# Microcontroller.net
KiCad netlist of a schematic drawn in Altium Designer
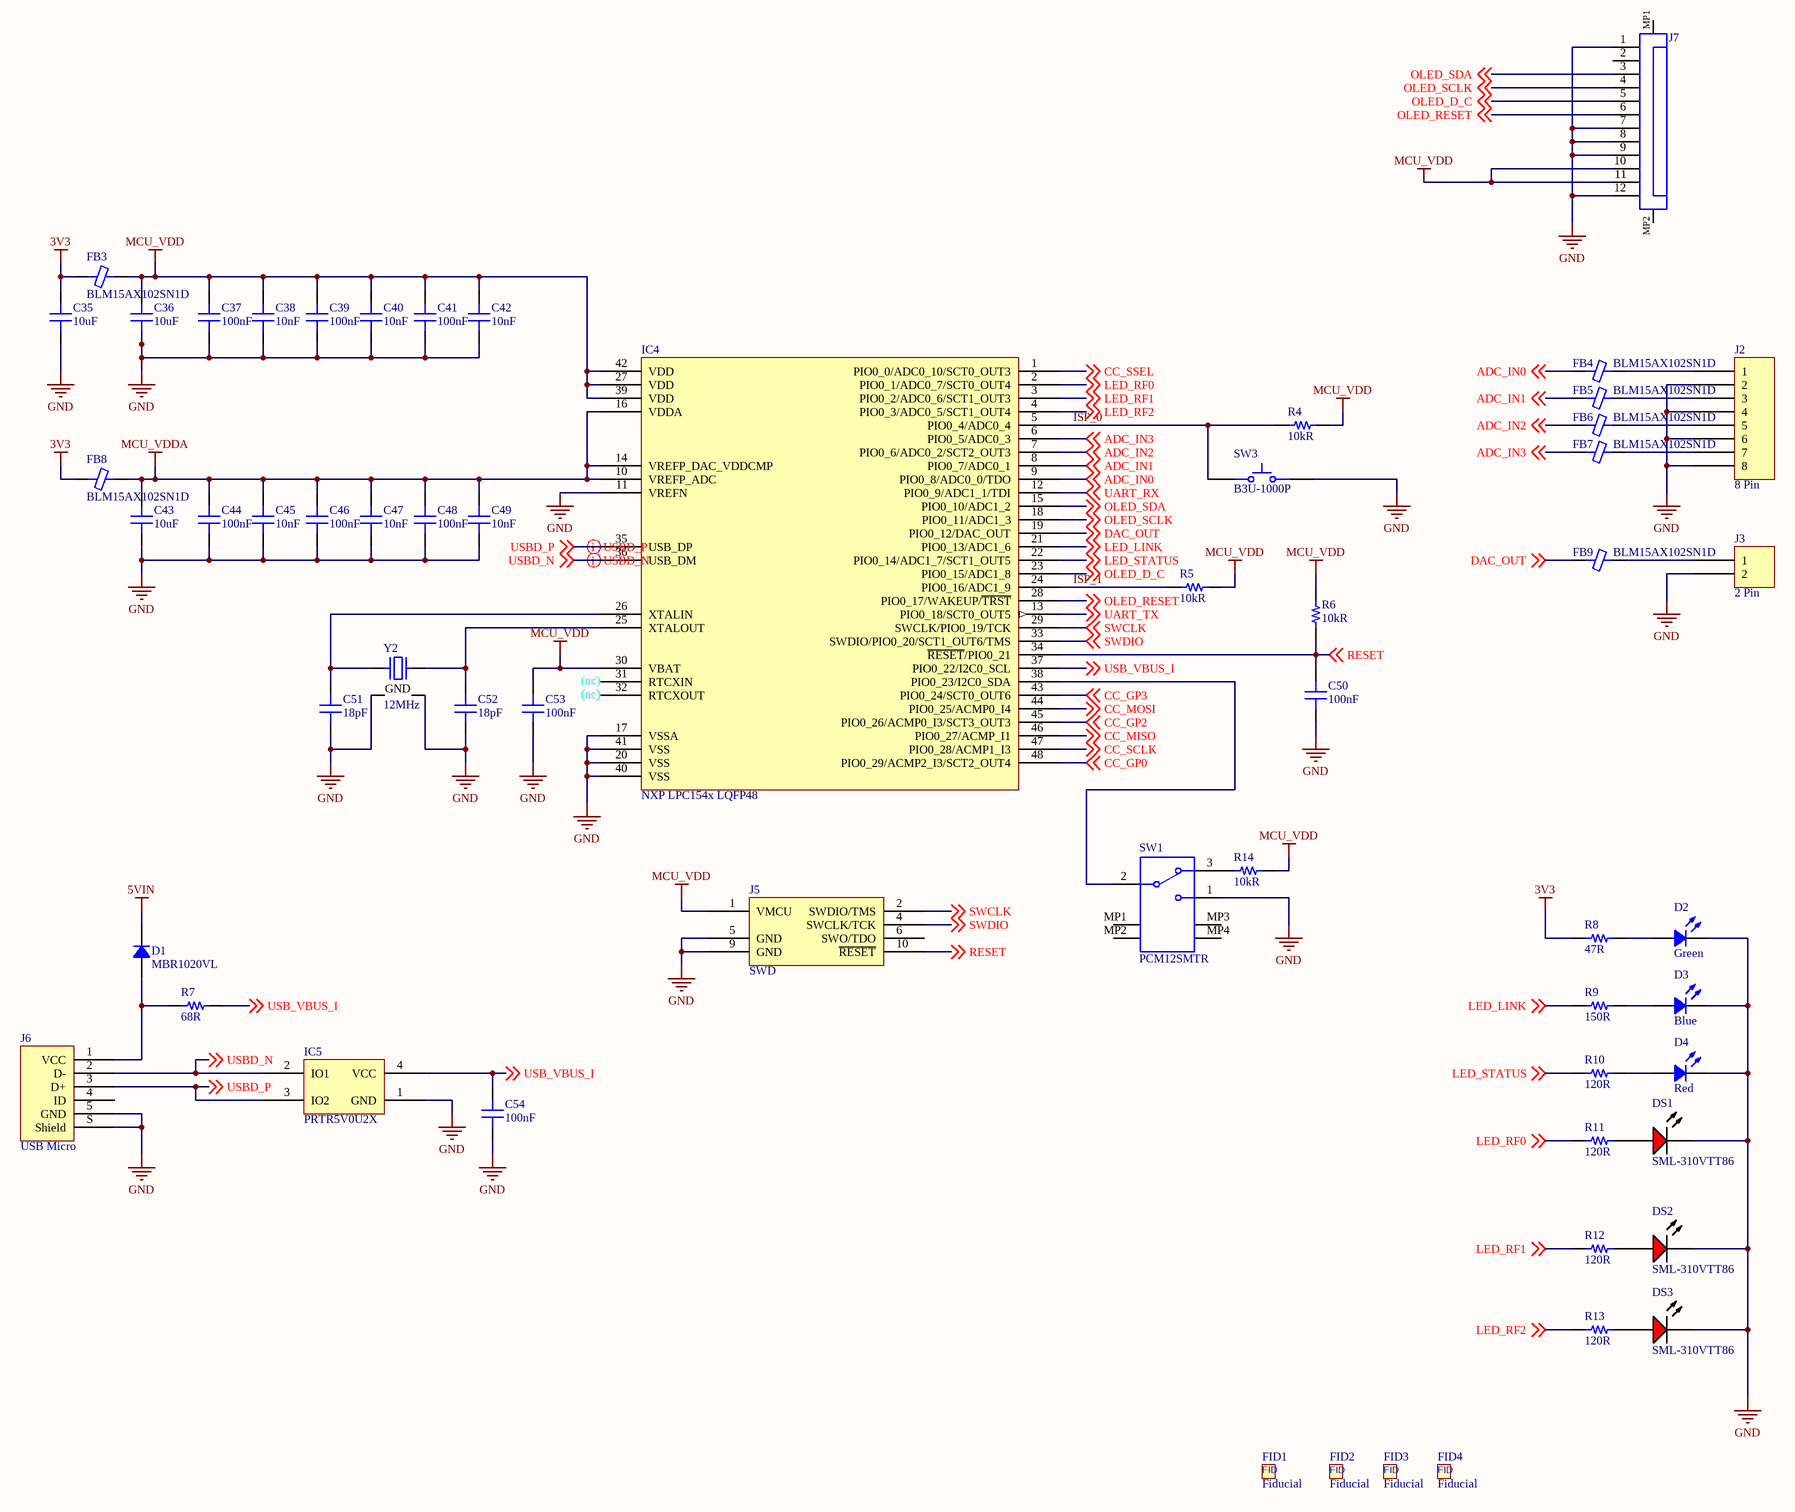
[diagram p0: Microcontroller.SchDoc]

(export (version "E")
  (design (tool "Eeschema 10.0.6"))
  (components
    (comp (ref "C35")
      (value "10uF")
      (footprint "CAP 0805/2012")
      (description "Cap Ceramic 10uF 10V X5R 10% SMD 0805 85C Embossed T/R")
      (fields (field (name "TOLERANCE") "10%") (field (name "VOLTAGE") "10V"))
      (libsource (lib "SCH - PASSIVES - CAPACITOR") (part "Capacitor"))
    )
    (comp (ref "C36")
      (value "10uF")
      (footprint "CAP 0805/2012")
      (description "Cap Ceramic 10uF 10V X5R 10% SMD 0805 85C Embossed T/R")
      (fields (field (name "TOLERANCE") "10%") (field (name "VOLTAGE") "10V"))
      (libsource (lib "SCH - PASSIVES - CAPACITOR") (part "Capacitor"))
    )
    (comp (ref "C37")
      (value "100nF")
      (footprint "CAP 0402/1005")
      (description "Cap Ceramic 0.1uF 10V X5R 20% Pad SMD 0402 85C T/R")
      (fields (field (name "TOLERANCE") "20%"))
      (libsource (lib "SCH - PASSIVES - CAPACITOR") (part "Capacitor"))
    )
    (comp (ref "C38")
      (value "10nF")
      (footprint "CAP 0402/1005")
      (description "TAIYO YUDEN - TMK105B7103KV-F - CERAMIC CAPACITOR 0.01UF, 25V, X7R, 10%, 0402, FULL REEL")
      (fields (field (name "TOLERANCE") "10%") (field (name "VOLTAGE") "25V"))
      (libsource (lib "SCH - PASSIVES - CAPACITOR") (part "Capacitor"))
    )
    (comp (ref "C39")
      (value "100nF")
      (footprint "CAP 0402/1005")
      (description "Cap Ceramic 0.1uF 10V X5R 20% Pad SMD 0402 85C T/R")
      (fields (field (name "TOLERANCE") "20%"))
      (libsource (lib "SCH - PASSIVES - CAPACITOR") (part "Capacitor"))
    )
    (comp (ref "C40")
      (value "10nF")
      (footprint "CAP 0402/1005")
      (description "TAIYO YUDEN - TMK105B7103KV-F - CERAMIC CAPACITOR 0.01UF, 25V, X7R, 10%, 0402, FULL REEL")
      (fields (field (name "TOLERANCE") "10%") (field (name "VOLTAGE") "25V"))
      (libsource (lib "SCH - PASSIVES - CAPACITOR") (part "Capacitor"))
    )
    (comp (ref "C41")
      (value "100nF")
      (footprint "CAP 0402/1005")
      (description "Cap Ceramic 0.1uF 10V X5R 20% Pad SMD 0402 85C T/R")
      (fields (field (name "TOLERANCE") "20%"))
      (libsource (lib "SCH - PASSIVES - CAPACITOR") (part "Capacitor"))
    )
    (comp (ref "C42")
      (value "10nF")
      (footprint "CAP 0402/1005")
      (description "TAIYO YUDEN - TMK105B7103KV-F - CERAMIC CAPACITOR 0.01UF, 25V, X7R, 10%, 0402, FULL REEL")
      (fields (field (name "TOLERANCE") "10%") (field (name "VOLTAGE") "25V"))
      (libsource (lib "SCH - PASSIVES - CAPACITOR") (part "Capacitor"))
    )
    (comp (ref "C43")
      (value "10uF")
      (footprint "CAP 0805/2012")
      (description "Cap Ceramic 10uF 10V X5R 10% SMD 0805 85C Embossed T/R")
      (fields (field (name "TOLERANCE") "10%") (field (name "VOLTAGE") "10V"))
      (libsource (lib "SCH - PASSIVES - CAPACITOR") (part "Capacitor"))
    )
    (comp (ref "C44")
      (value "100nF")
      (footprint "CAP 0402/1005")
      (description "Cap Ceramic 0.1uF 10V X5R 20% Pad SMD 0402 85C T/R")
      (fields (field (name "TOLERANCE") "20%"))
      (libsource (lib "SCH - PASSIVES - CAPACITOR") (part "Capacitor"))
    )
    (comp (ref "C45")
      (value "10nF")
      (footprint "CAP 0402/1005")
      (description "TAIYO YUDEN - TMK105B7103KV-F - CERAMIC CAPACITOR 0.01UF, 25V, X7R, 10%, 0402, FULL REEL")
      (fields (field (name "TOLERANCE") "10%") (field (name "VOLTAGE") "25V"))
      (libsource (lib "SCH - PASSIVES - CAPACITOR") (part "Capacitor"))
    )
    (comp (ref "C46")
      (value "100nF")
      (footprint "CAP 0402/1005")
      (description "Cap Ceramic 0.1uF 10V X5R 20% Pad SMD 0402 85C T/R")
      (fields (field (name "TOLERANCE") "20%"))
      (libsource (lib "SCH - PASSIVES - CAPACITOR") (part "Capacitor"))
    )
    (comp (ref "C47")
      (value "10nF")
      (footprint "CAP 0402/1005")
      (description "TAIYO YUDEN - TMK105B7103KV-F - CERAMIC CAPACITOR 0.01UF, 25V, X7R, 10%, 0402, FULL REEL")
      (fields (field (name "TOLERANCE") "10%") (field (name "VOLTAGE") "25V"))
      (libsource (lib "SCH - PASSIVES - CAPACITOR") (part "Capacitor"))
    )
    (comp (ref "C48")
      (value "100nF")
      (footprint "CAP 0402/1005")
      (description "Cap Ceramic 0.1uF 10V X5R 20% Pad SMD 0402 85C T/R")
      (fields (field (name "TOLERANCE") "20%"))
      (libsource (lib "SCH - PASSIVES - CAPACITOR") (part "Capacitor"))
    )
    (comp (ref "C49")
      (value "10nF")
      (footprint "CAP 0402/1005")
      (description "TAIYO YUDEN - TMK105B7103KV-F - CERAMIC CAPACITOR 0.01UF, 25V, X7R, 10%, 0402, FULL REEL")
      (fields (field (name "TOLERANCE") "10%") (field (name "VOLTAGE") "25V"))
      (libsource (lib "SCH - PASSIVES - CAPACITOR") (part "Capacitor"))
    )
    (comp (ref "C50")
      (value "100nF")
      (footprint "CAP 0402/1005")
      (description "Cap Ceramic 0.1uF 10V X5R 20% Pad SMD 0402 85C T/R")
      (fields (field (name "TOLERANCE") "20%"))
      (libsource (lib "SCH - PASSIVES - CAPACITOR") (part "Capacitor"))
    )
    (comp (ref "C51")
      (value "18pF")
      (footprint "CAP 0402/1005")
      (description "CAP CER 18PF 50V C0G/NPO 0402")
      (fields (field (name "TOLERANCE") "5%") (field (name "VOLTAGE") "50V"))
      (libsource (lib "SCH - PASSIVES - CAPACITOR") (part "Capacitor"))
    )
    (comp (ref "C52")
      (value "18pF")
      (footprint "CAP 0402/1005")
      (description "CAP CER 18PF 50V C0G/NPO 0402")
      (fields (field (name "TOLERANCE") "5%") (field (name "VOLTAGE") "50V"))
      (libsource (lib "SCH - PASSIVES - CAPACITOR") (part "Capacitor"))
    )
    (comp (ref "C53")
      (value "100nF")
      (footprint "CAP 0402/1005")
      (description "Cap Ceramic 0.1uF 10V X5R 20% Pad SMD 0402 85C T/R")
      (fields (field (name "TOLERANCE") "20%"))
      (libsource (lib "SCH - PASSIVES - CAPACITOR") (part "Capacitor"))
    )
    (comp (ref "C54")
      (value "100nF")
      (footprint "CAP 0402/1005")
      (description "Cap Ceramic 0.1uF 10V X5R 20% Pad SMD 0402 85C T/R")
      (fields (field (name "TOLERANCE") "20%"))
      (libsource (lib "SCH - PASSIVES - CAPACITOR") (part "Capacitor"))
    )
    (comp (ref "D1")
      (value "MBR1020VL")
      (footprint "SOD123F")
      (description "DIODE SCHOTTKY 20V 1A SOD123F")
      (libsource (lib "SCH - DIODES - DIODE") (part "Diode"))
    )
    (comp (ref "D2")
      (value "Green")
      (footprint "LED 0603/1608 GREEN")
      (description "0603 green led allngap 571nm-574nm water clear 18-71mcd 130d")
      (libsource (lib "SCH - DIODES - LED") (part "LED"))
    )
    (comp (ref "D3")
      (value "Blue")
      (footprint "LED 0603/1608 BLUE")
      (description "LED Uni-Color Blue 468nm 2-Pin Chip 0603(1608Metric) T/R")
      (libsource (lib "SCH - DIODES - LED") (part "LED"))
    )
    (comp (ref "D4")
      (value "Red")
      (footprint "LED 0603/1608 RED")
      (description "LED RED DIFFUSED 1608 SMD")
      (libsource (lib "SCH - DIODES - LED") (part "LED"))
    )
    (comp (ref "DS1")
      (value "SML-310VTT86")
      (footprint "ROHM-SML-31X_V")
      (fields (field (name "MANUFACTURER") "Rohm"))
      (libsource (lib "Altium Content Vault") (part "LED-RED-AK-2"))
    )
    (comp (ref "DS2")
      (value "SML-310VTT86")
      (footprint "ROHM-SML-31X_V")
      (fields (field (name "MANUFACTURER") "Rohm"))
      (libsource (lib "Altium Content Vault") (part "LED-RED-AK-2"))
    )
    (comp (ref "DS3")
      (value "SML-310VTT86")
      (footprint "ROHM-SML-31X_V")
      (fields (field (name "MANUFACTURER") "Rohm"))
      (libsource (lib "Altium Content Vault") (part "LED-RED-AK-2"))
    )
    (comp (ref "FB3")
      (value "BLM15AX102SN1D")
      (footprint "FER 0402/1005")
      (description "Ferrite Beads Multi-Layer 1KOhm 25% 100MHz 350mA 490mOhm DCR 0402 T/R")
      (fields (field (name "TOLERANCE") "25%"))
      (libsource (lib "SCH - PASSIVES - FERRITE CHIP") (part "Ferrite Chip"))
    )
    (comp (ref "FB4")
      (value "BLM15AX102SN1D")
      (footprint "FER 0402/1005")
      (description "Ferrite Beads Multi-Layer 1KOhm 25% 100MHz 350mA 490mOhm DCR 0402 T/R")
      (fields (field (name "TOLERANCE") "25%"))
      (libsource (lib "SCH - PASSIVES - FERRITE CHIP") (part "Ferrite Chip"))
    )
    (comp (ref "FB5")
      (value "BLM15AX102SN1D")
      (footprint "FER 0402/1005")
      (description "Ferrite Beads Multi-Layer 1KOhm 25% 100MHz 350mA 490mOhm DCR 0402 T/R")
      (fields (field (name "TOLERANCE") "25%"))
      (libsource (lib "SCH - PASSIVES - FERRITE CHIP") (part "Ferrite Chip"))
    )
    (comp (ref "FB6")
      (value "BLM15AX102SN1D")
      (footprint "FER 0402/1005")
      (description "Ferrite Beads Multi-Layer 1KOhm 25% 100MHz 350mA 490mOhm DCR 0402 T/R")
      (fields (field (name "TOLERANCE") "25%"))
      (libsource (lib "SCH - PASSIVES - FERRITE CHIP") (part "Ferrite Chip"))
    )
    (comp (ref "FB7")
      (value "BLM15AX102SN1D")
      (footprint "FER 0402/1005")
      (description "Ferrite Beads Multi-Layer 1KOhm 25% 100MHz 350mA 490mOhm DCR 0402 T/R")
      (fields (field (name "TOLERANCE") "25%"))
      (libsource (lib "SCH - PASSIVES - FERRITE CHIP") (part "Ferrite Chip"))
    )
    (comp (ref "FB8")
      (value "BLM15AX102SN1D")
      (footprint "FER 0402/1005")
      (description "Ferrite Beads Multi-Layer 1KOhm 25% 100MHz 350mA 490mOhm DCR 0402 T/R")
      (fields (field (name "TOLERANCE") "25%"))
      (libsource (lib "SCH - PASSIVES - FERRITE CHIP") (part "Ferrite Chip"))
    )
    (comp (ref "FB9")
      (value "BLM15AX102SN1D")
      (footprint "FER 0402/1005")
      (description "Ferrite Beads Multi-Layer 1KOhm 25% 100MHz 350mA 490mOhm DCR 0402 T/R")
      (fields (field (name "TOLERANCE") "25%"))
      (libsource (lib "SCH - PASSIVES - FERRITE CHIP") (part "Ferrite Chip"))
    )
    (comp (ref "FID1") (value "Fiducial") (footprint "Fiducial") (libsource (lib "Useful") (part "Fiducial")))
    (comp (ref "FID2") (value "Fiducial") (footprint "Fiducial") (libsource (lib "Useful") (part "Fiducial")))
    (comp (ref "FID3") (value "Fiducial") (footprint "Fiducial") (libsource (lib "Useful") (part "Fiducial")))
    (comp (ref "FID4") (value "Fiducial") (footprint "Fiducial") (libsource (lib "Useful") (part "Fiducial")))
    (comp (ref "IC4")
      (value "NXP LPC154x LQFP48")
      (footprint "NXP LQFP-48 7x7mm")
      (description "IC MCU 32BIT 256KB FLASH 48LQFP")
      (libsource (lib "SCH - ARM CORTEX - NXP LPC154X LQFP48") (part "NXP LPC154x LQFP48"))
    )
    (comp (ref "IC5")
      (value "PRTR5V0U2X")
      (footprint "SOT143B")
      (description "TVS DIODE 5.5V SOT143B")
      (libsource (lib "SCH - DIODES - NXP PRTR5V0U2X") (part "NXP PRTR5V0U2X"))
    )
    (comp (ref "J2")
      (value "8 Pin")
      (footprint "FCI 06-381-8PIN")
      (description "TERM BLOCK HDR 8POS 90DEG 3.81MM")
      (libsource (lib "SCH - CONNECTORS - 8 PIN") (part "8 Pin"))
    )
    (comp (ref "J3")
      (value "2 Pin")
      (footprint "FCI 06-381-2PIN")
      (description "TERM BLOCK HDR 2POS 90DEG 3.81MM")
      (libsource (lib "SCH - CONNECTORS - 2 PIN") (part "2 Pin"))
    )
    (comp (ref "J5") (value "SWD") (footprint "10 Pin SWD") (libsource (lib "Useful") (part "SWD")))
    (comp (ref "J6")
      (value "USB Micro")
      (footprint "FCI USB 10118193-0001LF")
      (description "CONN RCPT USB2.0 MICRO B SMD R/A")
      (libsource (lib "SCH - CONNECTORS - USB 2.0 TYPE B MICRO") (part "USB 2.0 Type B Micro"))
    )
    (comp (ref "J7")
      (value "687112183722")
      (footprint "687112183722")
      (description "SMT ZIF Connectors Low Profile WR-FPC, Horizontal, Bottom Contact, pitch 0.5 mm, 12 pins")
      (fields (field (name "MANUFACTURER") "Wurth Elektronik") (field (name "PUBLISHER") "WurthElektronik"))
      (libsource (lib "Altium Content Vault") (part "WE-68X1121XXX22-12"))
    )
    (comp (ref "R4")
      (value "10kR")
      (footprint "RES 0402/1005")
      (description "RES 10K OHM 5% 1/16W 0402")
      (fields (field (name "TOLERANCE") "5%"))
      (libsource (lib "SCH - PASSIVES - RESISTOR") (part "Resistor"))
    )
    (comp (ref "R5")
      (value "10kR")
      (footprint "RES 0402/1005")
      (description "RES 10K OHM 5% 1/16W 0402")
      (fields (field (name "TOLERANCE") "5%"))
      (libsource (lib "SCH - PASSIVES - RESISTOR") (part "Resistor"))
    )
    (comp (ref "R6")
      (value "10kR")
      (footprint "RES 0402/1005")
      (description "RES 10K OHM 5% 1/16W 0402")
      (fields (field (name "TOLERANCE") "5%"))
      (libsource (lib "SCH - PASSIVES - RESISTOR") (part "Resistor"))
    )
    (comp (ref "R7")
      (value "68R")
      (footprint "RES 0402/1005")
      (description "RES SMD 68 OHM 5% 1/16W 0402")
      (fields (field (name "TOLERANCE") "5%"))
      (libsource (lib "SCH - PASSIVES - RESISTOR") (part "Resistor"))
    )
    (comp (ref "R8")
      (value "47R")
      (footprint "RES 0402/1005")
      (description "KOA SPEAR ELECTRONICS - RK73B1JTTD470J - RES, 47R, 5%, 0.1W, 0603, THICK FILM")
      (fields (field (name "TOLERANCE") "5%"))
      (libsource (lib "SCH - PASSIVES - RESISTOR") (part "Resistor"))
    )
    (comp (ref "R9")
      (value "150R")
      (footprint "RES 0402/1005")
      (description "Res Thick Film 0603 150 Ohm 5% 0.1W(1/10W) ±200ppm/C Molded SMD Automotive Punched Paper T/R")
      (fields (field (name "TOLERANCE") "5%"))
      (libsource (lib "SCH - PASSIVES - RESISTOR") (part "Resistor"))
    )
    (comp (ref "R10")
      (value "120R")
      (footprint "RES 0402/1005")
      (fields (field (name "TOLERANCE") "5%"))
      (libsource (lib "SCH - PASSIVES - RESISTOR") (part "Resistor"))
    )
    (comp (ref "R11")
      (value "120R")
      (footprint "RES 0402/1005")
      (fields (field (name "TOLERANCE") "5%"))
      (libsource (lib "SCH - PASSIVES - RESISTOR") (part "Resistor"))
    )
    (comp (ref "R12")
      (value "120R")
      (footprint "RES 0402/1005")
      (fields (field (name "TOLERANCE") "5%"))
      (libsource (lib "SCH - PASSIVES - RESISTOR") (part "Resistor"))
    )
    (comp (ref "R13")
      (value "120R")
      (footprint "RES 0402/1005")
      (fields (field (name "TOLERANCE") "5%"))
      (libsource (lib "SCH - PASSIVES - RESISTOR") (part "Resistor"))
    )
    (comp (ref "R14")
      (value "10kR")
      (footprint "RES 0402/1005")
      (description "RES 10K OHM 5% 1/16W 0402")
      (fields (field (name "TOLERANCE") "5%"))
      (libsource (lib "SCH - PASSIVES - RESISTOR") (part "Resistor"))
    )
    (comp (ref "SW1")
      (value "PCM12SMTR")
      (footprint "CKCP-PCM12SMTR_V")
      (description "Ultraminiature Slide Switch, SPDT, 0.3 A, 6 V, -20 to 85 degC, 3-Pin SMD, RoHS, Tape and Reel")
      (fields (field (name "MANUFACTURER") "C&K Components"))
      (libsource (lib "Altium Content Vault") (part "SW-SPDT-3_A"))
    )
    (comp (ref "SW3")
      (value "B3U-1000P")
      (footprint "OMRON-B3U-1000_V")
      (description "Ultra-Small Tactile Switch, 0.05 A, 12 V, -25 to 70 degC, 2-Pin SMD, RoHS, Tape and Reel")
      (fields (field (name "MANUFACTURER") "Omron Electronic Components"))
      (libsource (lib "Altium Content Vault") (part "SW-SPST-NO-2"))
    )
    (comp (ref "Y2")
      (value "12MHz")
      (footprint "ABRACON ABM8G")
      (description "CRYSTAL 12.0000MHZ 18PF SMD")
      (fields (field (name "TOLERANCE") "20ppm"))
      (libsource (lib "SCH - CRYSTALS - ABRACON CRYSTAL ABM8G") (part "Abracon Crystal ABM8G"))
    )
  )
  (nets
    (net (code "1") (name "/ISP_0") (class "Default")
      (node (ref "IC4") (pin "5") (pinfunction "PIO0_4/ADC0_4_5") (pintype "passive"))
      (node (ref "R4") (pin "2") (pinfunction "2_2") (pintype "passive"))
      (node (ref "SW3") (pin "1") (pinfunction "1_1") (pintype "passive"))
    )
    (net (code "2") (name "/ISP_1") (class "Default")
      (node (ref "IC4") (pin "24") (pinfunction "PIO0_16/ADC1_9_24") (pintype "passive"))
      (node (ref "R5") (pin "2") (pinfunction "2_2") (pintype "passive"))
    )
    (net (code "3") (name "3V3") (class "Default")
      (node (ref "C35") (pin "2") (pinfunction "2_2") (pintype "passive"))
      (node (ref "FB3") (pin "2") (pinfunction "2_2") (pintype "passive"))
      (node (ref "FB8") (pin "2") (pinfunction "2_2") (pintype "passive"))
      (node (ref "R8") (pin "1") (pinfunction "1_1") (pintype "passive"))
    )
    (net (code "4") (name "5VIN") (class "Default")
      (node (ref "D1") (pin "2") (pinfunction "2_2") (pintype "passive"))
    )
    (net (code "5") (name "ADC_IN0") (class "Default")
      (node (ref "FB4") (pin "2") (pinfunction "2_2") (pintype "passive"))
      (node (ref "IC4") (pin "9") (pinfunction "PIO0_8/ADC0_0/TDO_9") (pintype "passive"))
    )
    (net (code "6") (name "ADC_IN1") (class "Default")
      (node (ref "FB5") (pin "2") (pinfunction "2_2") (pintype "passive"))
      (node (ref "IC4") (pin "8") (pinfunction "PIO0_7/ADC0_1_8") (pintype "passive"))
    )
    (net (code "7") (name "ADC_IN2") (class "Default")
      (node (ref "FB6") (pin "2") (pinfunction "2_2") (pintype "passive"))
      (node (ref "IC4") (pin "7") (pinfunction "PIO0_6/ADC0_2/SCT2_OUT3_7") (pintype "passive"))
    )
    (net (code "8") (name "ADC_IN3") (class "Default")
      (node (ref "FB7") (pin "2") (pinfunction "2_2") (pintype "passive"))
      (node (ref "IC4") (pin "6") (pinfunction "PIO0_5/ADC0_3_6") (pintype "passive"))
    )
    (net (code "9") (name "CC_GP0") (class "Default")
      (node (ref "IC4") (pin "48") (pinfunction "PIO0_29/ACMP2_I3/SCT2_OUT4_48") (pintype "passive"))
    )
    (net (code "10") (name "CC_GP2") (class "Default")
      (node (ref "IC4") (pin "45") (pinfunction "PIO0_26/ACMP0_I3/SCT3_OUT3_45") (pintype "passive"))
    )
    (net (code "11") (name "CC_GP3") (class "Default")
      (node (ref "IC4") (pin "43") (pinfunction "PIO0_24/SCT0_OUT6_43") (pintype "passive"))
    )
    (net (code "12") (name "CC_MISO") (class "Default")
      (node (ref "IC4") (pin "46") (pinfunction "PIO0_27/ACMP_I1_46") (pintype "passive"))
    )
    (net (code "13") (name "CC_MOSI") (class "Default")
      (node (ref "IC4") (pin "44") (pinfunction "PIO0_25/ACMP0_I4_44") (pintype "passive"))
    )
    (net (code "14") (name "CC_SCLK") (class "Default")
      (node (ref "IC4") (pin "47") (pinfunction "PIO0_28/ACMP1_I3_47") (pintype "passive"))
    )
    (net (code "15") (name "CC_SSEL") (class "Default")
      (node (ref "IC4") (pin "1") (pinfunction "PIO0_0/ADC0_10/SCT0_OUT3_1") (pintype "passive"))
    )
    (net (code "16") (name "DAC_OUT") (class "Default")
      (node (ref "FB9") (pin "2") (pinfunction "2_2") (pintype "passive"))
      (node (ref "IC4") (pin "19") (pinfunction "PIO0_12/DAC_OUT_19") (pintype "passive"))
    )
    (net (code "17") (name "GND") (class "Default")
      (node (ref "C35") (pin "1") (pinfunction "1_1") (pintype "passive"))
      (node (ref "C36") (pin "1") (pinfunction "1_1") (pintype "passive"))
      (node (ref "C37") (pin "1") (pinfunction "1_1") (pintype "passive"))
      (node (ref "C38") (pin "1") (pinfunction "1_1") (pintype "passive"))
      (node (ref "C39") (pin "1") (pinfunction "1_1") (pintype "passive"))
      (node (ref "C40") (pin "1") (pinfunction "1_1") (pintype "passive"))
      (node (ref "C41") (pin "1") (pinfunction "1_1") (pintype "passive"))
      (node (ref "C42") (pin "1") (pinfunction "1_1") (pintype "passive"))
      (node (ref "C43") (pin "1") (pinfunction "1_1") (pintype "passive"))
      (node (ref "C44") (pin "1") (pinfunction "1_1") (pintype "passive"))
      (node (ref "C45") (pin "1") (pinfunction "1_1") (pintype "passive"))
      (node (ref "C46") (pin "1") (pinfunction "1_1") (pintype "passive"))
      (node (ref "C47") (pin "1") (pinfunction "1_1") (pintype "passive"))
      (node (ref "C48") (pin "1") (pinfunction "1_1") (pintype "passive"))
      (node (ref "C49") (pin "1") (pinfunction "1_1") (pintype "passive"))
      (node (ref "C50") (pin "1") (pinfunction "1_1") (pintype "passive"))
      (node (ref "C51") (pin "1") (pinfunction "1_1") (pintype "passive"))
      (node (ref "C52") (pin "1") (pinfunction "1_1") (pintype "passive"))
      (node (ref "C53") (pin "1") (pinfunction "1_1") (pintype "passive"))
      (node (ref "C54") (pin "1") (pinfunction "1_1") (pintype "passive"))
      (node (ref "D2") (pin "2") (pinfunction "2_2") (pintype "passive"))
      (node (ref "D3") (pin "2") (pinfunction "2_2") (pintype "passive"))
      (node (ref "D4") (pin "2") (pinfunction "2_2") (pintype "passive"))
      (node (ref "DS1") (pin "2") (pinfunction "K_2") (pintype "passive"))
      (node (ref "DS2") (pin "2") (pinfunction "K_2") (pintype "passive"))
      (node (ref "DS3") (pin "2") (pinfunction "K_2") (pintype "passive"))
      (node (ref "IC4") (pin "11") (pinfunction "VREFN_11") (pintype "passive"))
      (node (ref "IC4") (pin "17") (pinfunction "VSSA_17") (pintype "passive"))
      (node (ref "IC4") (pin "20") (pinfunction "VSS_20") (pintype "passive"))
      (node (ref "IC4") (pin "40") (pinfunction "VSS_40") (pintype "passive"))
      (node (ref "IC4") (pin "41") (pinfunction "VSS_41") (pintype "passive"))
      (node (ref "IC5") (pin "1") (pinfunction "GND_1") (pintype "passive"))
      (node (ref "J2") (pin "2") (pinfunction "2_2") (pintype "passive"))
      (node (ref "J2") (pin "4") (pinfunction "4_4") (pintype "passive"))
      (node (ref "J2") (pin "6") (pinfunction "6_6") (pintype "passive"))
      (node (ref "J2") (pin "8") (pinfunction "8_8") (pintype "passive"))
      (node (ref "J3") (pin "2") (pinfunction "2_2") (pintype "passive"))
      (node (ref "J5") (pin "5") (pinfunction "GND_5") (pintype "passive"))
      (node (ref "J5") (pin "9") (pinfunction "GND_9") (pintype "passive"))
      (node (ref "J6") (pin "5") (pinfunction "GND_5") (pintype "passive"))
      (node (ref "J6") (pin "S") (pinfunction "Shield_S") (pintype "passive"))
      (node (ref "J7") (pin "1") (pinfunction "1_1") (pintype "passive"))
      (node (ref "J7") (pin "12") (pinfunction "12_12") (pintype "passive"))
      (node (ref "J7") (pin "7") (pinfunction "7_7") (pintype "passive"))
      (node (ref "J7") (pin "8") (pinfunction "8_8") (pintype "passive"))
      (node (ref "J7") (pin "9") (pinfunction "9_9") (pintype "passive"))
      (node (ref "SW1") (pin "1") (pinfunction "1_1") (pintype "passive"))
      (node (ref "SW3") (pin "2") (pinfunction "2_2") (pintype "passive"))
      (node (ref "Y2") (pin "2") (pinfunction "GND_2") (pintype "passive"))
      (node (ref "Y2") (pin "4") (pinfunction "GND_4") (pintype "passive"))
    )
    (net (code "18") (name "LED_LINK") (class "Default")
      (node (ref "IC4") (pin "21") (pinfunction "PIO0_13/ADC1_6_21") (pintype "passive"))
      (node (ref "R9") (pin "1") (pinfunction "1_1") (pintype "passive"))
    )
    (net (code "19") (name "LED_RF0") (class "Default")
      (node (ref "IC4") (pin "2") (pinfunction "PIO0_1/ADC0_7/SCT0_OUT4_2") (pintype "passive"))
      (node (ref "R11") (pin "1") (pinfunction "1_1") (pintype "passive"))
    )
    (net (code "20") (name "LED_RF1") (class "Default")
      (node (ref "IC4") (pin "3") (pinfunction "PIO0_2/ADC0_6/SCT1_OUT3_3") (pintype "passive"))
      (node (ref "R12") (pin "1") (pinfunction "1_1") (pintype "passive"))
    )
    (net (code "21") (name "LED_RF2") (class "Default")
      (node (ref "IC4") (pin "4") (pinfunction "PIO0_3/ADC0_5/SCT1_OUT4_4") (pintype "passive"))
      (node (ref "R13") (pin "1") (pinfunction "1_1") (pintype "passive"))
    )
    (net (code "22") (name "LED_STATUS") (class "Default")
      (node (ref "IC4") (pin "22") (pinfunction "PIO0_14/ADC1_7/SCT1_OUT5_22") (pintype "passive"))
      (node (ref "R10") (pin "1") (pinfunction "1_1") (pintype "passive"))
    )
    (net (code "23") (name "MCU_VDD") (class "Default")
      (node (ref "C36") (pin "2") (pinfunction "2_2") (pintype "passive"))
      (node (ref "C37") (pin "2") (pinfunction "2_2") (pintype "passive"))
      (node (ref "C38") (pin "2") (pinfunction "2_2") (pintype "passive"))
      (node (ref "C39") (pin "2") (pinfunction "2_2") (pintype "passive"))
      (node (ref "C40") (pin "2") (pinfunction "2_2") (pintype "passive"))
      (node (ref "C41") (pin "2") (pinfunction "2_2") (pintype "passive"))
      (node (ref "C42") (pin "2") (pinfunction "2_2") (pintype "passive"))
      (node (ref "C53") (pin "2") (pinfunction "2_2") (pintype "passive"))
      (node (ref "FB3") (pin "1") (pinfunction "1_1") (pintype "passive"))
      (node (ref "IC4") (pin "27") (pinfunction "VDD_27") (pintype "passive"))
      (node (ref "IC4") (pin "30") (pinfunction "VBAT_30") (pintype "passive"))
      (node (ref "IC4") (pin "39") (pinfunction "VDD_39") (pintype "passive"))
      (node (ref "IC4") (pin "42") (pinfunction "VDD_42") (pintype "passive"))
      (node (ref "J5") (pin "1") (pinfunction "VMCU_1") (pintype "passive"))
      (node (ref "J7") (pin "10") (pinfunction "10_10") (pintype "passive"))
      (node (ref "J7") (pin "11") (pinfunction "11_11") (pintype "passive"))
      (node (ref "R14") (pin "1") (pinfunction "1_1") (pintype "passive"))
      (node (ref "R4") (pin "1") (pinfunction "1_1") (pintype "passive"))
      (node (ref "R5") (pin "1") (pinfunction "1_1") (pintype "passive"))
      (node (ref "R6") (pin "1") (pinfunction "1_1") (pintype "passive"))
    )
    (net (code "24") (name "MCU_VDDA") (class "Default")
      (node (ref "C43") (pin "2") (pinfunction "2_2") (pintype "passive"))
      (node (ref "C44") (pin "2") (pinfunction "2_2") (pintype "passive"))
      (node (ref "C45") (pin "2") (pinfunction "2_2") (pintype "passive"))
      (node (ref "C46") (pin "2") (pinfunction "2_2") (pintype "passive"))
      (node (ref "C47") (pin "2") (pinfunction "2_2") (pintype "passive"))
      (node (ref "C48") (pin "2") (pinfunction "2_2") (pintype "passive"))
      (node (ref "C49") (pin "2") (pinfunction "2_2") (pintype "passive"))
      (node (ref "FB8") (pin "1") (pinfunction "1_1") (pintype "passive"))
      (node (ref "IC4") (pin "10") (pinfunction "VREFP_ADC_10") (pintype "passive"))
      (node (ref "IC4") (pin "14") (pinfunction "VREFP_DAC_VDDCMP_14") (pintype "passive"))
      (node (ref "IC4") (pin "16") (pinfunction "VDDA_16") (pintype "passive"))
    )
    (net (code "25") (name "Net-(D2-Pad1)") (class "Default")
      (node (ref "D2") (pin "1") (pinfunction "1_1") (pintype "passive"))
      (node (ref "R8") (pin "2") (pinfunction "2_2") (pintype "passive"))
    )
    (net (code "26") (name "Net-(D3-Pad1)") (class "Default")
      (node (ref "D3") (pin "1") (pinfunction "1_1") (pintype "passive"))
      (node (ref "R9") (pin "2") (pinfunction "2_2") (pintype "passive"))
    )
    (net (code "27") (name "Net-(D4-Pad1)") (class "Default")
      (node (ref "D4") (pin "1") (pinfunction "1_1") (pintype "passive"))
      (node (ref "R10") (pin "2") (pinfunction "2_2") (pintype "passive"))
    )
    (net (code "28") (name "Net-(DS1-A)") (class "Default")
      (node (ref "DS1") (pin "1") (pinfunction "A_1") (pintype "passive"))
      (node (ref "R11") (pin "2") (pinfunction "2_2") (pintype "passive"))
    )
    (net (code "29") (name "Net-(DS2-A)") (class "Default")
      (node (ref "DS2") (pin "1") (pinfunction "A_1") (pintype "passive"))
      (node (ref "R12") (pin "2") (pinfunction "2_2") (pintype "passive"))
    )
    (net (code "30") (name "Net-(DS3-A)") (class "Default")
      (node (ref "DS3") (pin "1") (pinfunction "A_1") (pintype "passive"))
      (node (ref "R13") (pin "2") (pinfunction "2_2") (pintype "passive"))
    )
    (net (code "31") (name "Net-(FB4-Pad1)") (class "Default")
      (node (ref "FB4") (pin "1") (pinfunction "1_1") (pintype "passive"))
      (node (ref "J2") (pin "1") (pinfunction "1_1") (pintype "passive"))
    )
    (net (code "32") (name "Net-(FB5-Pad1)") (class "Default")
      (node (ref "FB5") (pin "1") (pinfunction "1_1") (pintype "passive"))
      (node (ref "J2") (pin "3") (pinfunction "3_3") (pintype "passive"))
    )
    (net (code "33") (name "Net-(FB6-Pad1)") (class "Default")
      (node (ref "FB6") (pin "1") (pinfunction "1_1") (pintype "passive"))
      (node (ref "J2") (pin "5") (pinfunction "5_5") (pintype "passive"))
    )
    (net (code "34") (name "Net-(FB7-Pad1)") (class "Default")
      (node (ref "FB7") (pin "1") (pinfunction "1_1") (pintype "passive"))
      (node (ref "J2") (pin "7") (pinfunction "7_7") (pintype "passive"))
    )
    (net (code "35") (name "Net-(FB9-Pad1)") (class "Default")
      (node (ref "FB9") (pin "1") (pinfunction "1_1") (pintype "passive"))
      (node (ref "J3") (pin "1") (pinfunction "1_1") (pintype "passive"))
    )
    (net (code "36") (name "Net-(IC4-PIO0_23{slash}I2C0_SDA)") (class "Default")
      (node (ref "IC4") (pin "38") (pinfunction "PIO0_23/I2C0_SDA_38") (pintype "passive"))
      (node (ref "SW1") (pin "2") (pinfunction "2_2") (pintype "passive"))
    )
    (net (code "37") (name "Net-(IC4-XTALIN)") (class "Default")
      (node (ref "C51") (pin "2") (pinfunction "2_2") (pintype "passive"))
      (node (ref "IC4") (pin "26") (pinfunction "XTALIN_26") (pintype "passive"))
      (node (ref "Y2") (pin "1") (pinfunction "1_1") (pintype "passive"))
    )
    (net (code "38") (name "Net-(IC4-XTALOUT)") (class "Default")
      (node (ref "C52") (pin "2") (pinfunction "2_2") (pintype "passive"))
      (node (ref "IC4") (pin "25") (pinfunction "XTALOUT_25") (pintype "passive"))
      (node (ref "Y2") (pin "3") (pinfunction "3_3") (pintype "passive"))
    )
    (net (code "39") (name "Net-(J6-VCC)") (class "Default")
      (node (ref "D1") (pin "1") (pinfunction "1_1") (pintype "passive"))
      (node (ref "J6") (pin "1") (pinfunction "VCC_1") (pintype "passive"))
      (node (ref "R7") (pin "2") (pinfunction "2_2") (pintype "passive"))
    )
    (net (code "40") (name "Net-(R14-Pad2)") (class "Default")
      (node (ref "R14") (pin "2") (pinfunction "2_2") (pintype "passive"))
      (node (ref "SW1") (pin "3") (pinfunction "3_3") (pintype "passive"))
    )
    (net (code "41") (name "OLED_D_C") (class "Default")
      (node (ref "IC4") (pin "23") (pinfunction "PIO0_15/ADC1_8_23") (pintype "passive"))
      (node (ref "J7") (pin "5") (pinfunction "5_5") (pintype "passive"))
    )
    (net (code "42") (name "OLED_RESET") (class "Default")
      (node (ref "IC4") (pin "28") (pinfunction "PIO0_17/WAKEUP/~{TRST}_28") (pintype "passive"))
      (node (ref "J7") (pin "6") (pinfunction "6_6") (pintype "passive"))
    )
    (net (code "43") (name "OLED_SCLK") (class "Default")
      (node (ref "IC4") (pin "18") (pinfunction "PIO0_11/ADC1_3_18") (pintype "passive"))
      (node (ref "J7") (pin "4") (pinfunction "4_4") (pintype "passive"))
    )
    (net (code "44") (name "OLED_SDA") (class "Default")
      (node (ref "IC4") (pin "15") (pinfunction "PIO0_10/ADC1_2_15") (pintype "passive"))
      (node (ref "J7") (pin "3") (pinfunction "3_3") (pintype "passive"))
    )
    (net (code "45") (name "RESET") (class "Default")
      (node (ref "C50") (pin "2") (pinfunction "2_2") (pintype "passive"))
      (node (ref "IC4") (pin "34") (pinfunction "~{RESET}/PIO0_21_34") (pintype "passive"))
      (node (ref "J5") (pin "10") (pinfunction "~{RESET}_10") (pintype "passive"))
      (node (ref "R6") (pin "2") (pinfunction "2_2") (pintype "passive"))
    )
    (net (code "46") (name "SWCLK") (class "Default")
      (node (ref "IC4") (pin "29") (pinfunction "SWCLK/PIO0_19/TCK_29") (pintype "passive"))
      (node (ref "J5") (pin "2") (pinfunction "SWDIO/TMS_2") (pintype "passive"))
    )
    (net (code "47") (name "SWDIO") (class "Default")
      (node (ref "IC4") (pin "33") (pinfunction "SWDIO/PIO0_20/SCT1_OUT6/TMS_33") (pintype "passive"))
      (node (ref "J5") (pin "4") (pinfunction "SWCLK/TCK_4") (pintype "passive"))
    )
    (net (code "48") (name "UART_RX") (class "Default")
      (node (ref "IC4") (pin "12") (pinfunction "PIO0_9/ADC1_1/TDI_12") (pintype "passive"))
    )
    (net (code "49") (name "UART_TX") (class "Default")
      (node (ref "IC4") (pin "13") (pinfunction "PIO0_18/SCT0_OUT5_13") (pintype "output"))
    )
    (net (code "50") (name "USBD_N") (class "Default")
      (node (ref "IC4") (pin "36") (pinfunction "USB_DM_36") (pintype "passive"))
      (node (ref "IC5") (pin "2") (pinfunction "IO1_2") (pintype "passive"))
      (node (ref "J6") (pin "2") (pinfunction "D-_2") (pintype "passive"))
    )
    (net (code "51") (name "USBD_P") (class "Default")
      (node (ref "IC4") (pin "35") (pinfunction "USB_DP_35") (pintype "passive"))
      (node (ref "IC5") (pin "3") (pinfunction "IO2_3") (pintype "passive"))
      (node (ref "J6") (pin "3") (pinfunction "D+_3") (pintype "passive"))
    )
    (net (code "52") (name "USB_VBUS_I") (class "Default")
      (node (ref "C54") (pin "2") (pinfunction "2_2") (pintype "passive"))
      (node (ref "IC4") (pin "37") (pinfunction "PIO0_22/I2C0_SCL_37") (pintype "passive"))
      (node (ref "IC5") (pin "4") (pinfunction "VCC_4") (pintype "passive"))
      (node (ref "R7") (pin "1") (pinfunction "1_1") (pintype "passive"))
    )
    (net (code "53") (name "unconnected-(IC4-RTCXIN-Pad31)") (class "Default")
      (node (ref "IC4") (pin "31") (pinfunction "RTCXIN_31") (pintype "passive"))
    )
    (net (code "54") (name "unconnected-(IC4-RTCXOUT-Pad32)") (class "Default")
      (node (ref "IC4") (pin "32") (pinfunction "RTCXOUT_32") (pintype "passive"))
    )
    (net (code "55") (name "unconnected-(J5-SWO{slash}TDO-Pad6)") (class "Default")
      (node (ref "J5") (pin "6") (pinfunction "SWO/TDO_6") (pintype "passive"))
    )
    (net (code "56") (name "unconnected-(J6-ID-Pad4)") (class "Default")
      (node (ref "J6") (pin "4") (pinfunction "ID_4") (pintype "passive"))
    )
    (net (code "57") (name "unconnected-(J7-Pad2)") (class "Default")
      (node (ref "J7") (pin "2") (pinfunction "2_2") (pintype "passive"))
    )
    (net (code "58") (name "unconnected-(J7-PadMP1)") (class "Default")
      (node (ref "J7") (pin "MP1") (pinfunction "MP1_MP1") (pintype "passive"))
    )
    (net (code "59") (name "unconnected-(J7-PadMP2)") (class "Default")
      (node (ref "J7") (pin "MP2") (pinfunction "MP2_MP2") (pintype "passive"))
    )
    (net (code "60") (name "unconnected-(SW1-PadMP1)") (class "Default")
      (node (ref "SW1") (pin "MP1") (pinfunction "MP1_MP1") (pintype "passive"))
    )
    (net (code "61") (name "unconnected-(SW1-PadMP2)") (class "Default")
      (node (ref "SW1") (pin "MP2") (pinfunction "MP2_MP2") (pintype "passive"))
    )
    (net (code "62") (name "unconnected-(SW1-PadMP3)") (class "Default")
      (node (ref "SW1") (pin "MP3") (pinfunction "MP3_MP3") (pintype "passive"))
    )
    (net (code "63") (name "unconnected-(SW1-PadMP4)") (class "Default")
      (node (ref "SW1") (pin "MP4") (pinfunction "MP4_MP4") (pintype "passive"))
    )
  )
)
